# ST_LINK_V2-1.net
KiCad netlist of a schematic drawn in Altium Designer
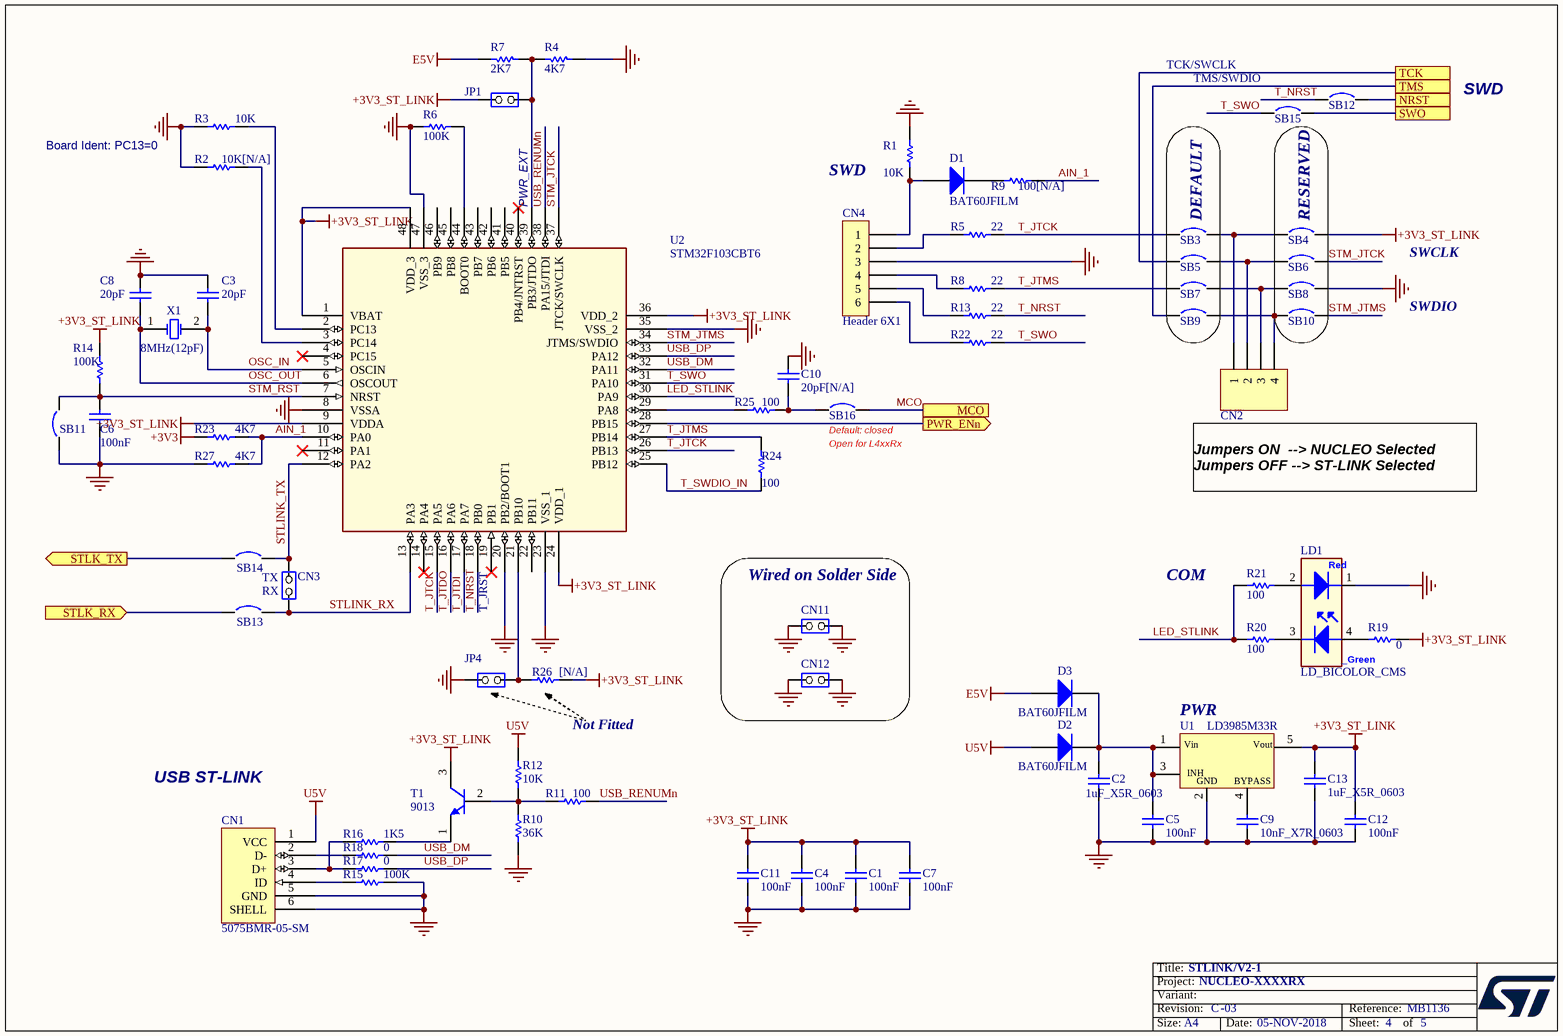
[diagram p0: ST_LINK_V2-1.SCHDOC]

(export (version "E")
  (design (tool "Eeschema 10.0.6"))
  (components
    (comp (ref "C1")
      (value "100nF")
      (footprint "0603C")
      (description "Capacitor 0402 / 0603 / 0805")
      (libsource (lib "MCD_TOOLS") (part "Capacitor_ST"))
    )
    (comp (ref "C2")
      (value "1uF_X5R_0603")
      (footprint "0603C")
      (description "0603  X5R 1µF")
      (fields (field (name "TOLERANCE") "10%"))
      (libsource (lib "MB963_1") (part "CAP SMD 0603  X5R 1µF 25V 10%"))
    )
    (comp (ref "C3")
      (value "20pF")
      (footprint "0603C")
      (description "Capacitor 0402 / 0603 / 0805")
      (libsource (lib "MCD_TOOLS") (part "Capacitor_ST"))
    )
    (comp (ref "C4")
      (value "100nF")
      (footprint "0603C")
      (description "Capacitor 0402 / 0603 / 0805")
      (libsource (lib "MCD_TOOLS") (part "Capacitor_ST"))
    )
    (comp (ref "C5")
      (value "100nF")
      (footprint "0603C")
      (description "Capacitor 0402 / 0603 / 0805")
      (libsource (lib "MCD_TOOLS") (part "Capacitor_ST"))
    )
    (comp (ref "C6")
      (value "100nF")
      (footprint "0603C")
      (description "Capacitor 0402 / 0603 / 0805")
      (libsource (lib "MCD_TOOLS") (part "Capacitor_ST"))
    )
    (comp (ref "C7")
      (value "100nF")
      (footprint "0603C")
      (description "Capacitor 0402 / 0603 / 0805")
      (libsource (lib "MCD_TOOLS") (part "Capacitor_ST"))
    )
    (comp (ref "C8")
      (value "20pF")
      (footprint "0603C")
      (description "Capacitor 0402 / 0603 / 0805")
      (libsource (lib "MCD_TOOLS") (part "Capacitor_ST"))
    )
    (comp (ref "C9")
      (value "10nF_X7R_0603")
      (footprint "0603C")
      (description "0603  X7R 10NF")
      (fields (field (name "TOLERANCE") "10%"))
      (libsource (lib "MB963_1") (part "CAP SMD 0603  X7R 10000PF 50V 10%"))
    )
    (comp (ref "C10")
      (value "20pF[N/A]")
      (footprint "0603C")
      (description "Capacitor 0402 / 0603 / 0805")
      (libsource (lib "MCD_TOOLS") (part "Capacitor_ST"))
    )
    (comp (ref "C11")
      (value "100nF")
      (footprint "0603C")
      (description "Capacitor 0402 / 0603 / 0805")
      (libsource (lib "MCD_TOOLS") (part "Capacitor_ST"))
    )
    (comp (ref "C12")
      (value "100nF")
      (footprint "0603C")
      (description "Capacitor 0402 / 0603 / 0805")
      (libsource (lib "MCD_TOOLS") (part "Capacitor_ST"))
    )
    (comp (ref "C13")
      (value "1uF_X5R_0603")
      (footprint "0603C")
      (description "0603  X5R 1µF")
      (fields (field (name "TOLERANCE") "10%"))
      (libsource (lib "MB963_1") (part "CAP SMD 0603  X5R 1µF 25V 10%"))
    )
    (comp (ref "CN1")
      (value "5075BMR-05-SM")
      (footprint "USB-MINI-B-SMD")
      (description "USB-MINI-typeB connector")
      (libsource (lib "MCD_TOOLS") (part "USB-MINI-typeB connector"))
    )
    (comp (ref "CN2")
      (value "Header 4")
      (footprint "1*4")
      (description "Header, 4-Pin, Single row")
      (fields (field (name "PUBLISHER") "Altium Limited"))
      (libsource (lib "Nucleo_64") (part "Header 4"))
    )
    (comp (ref "CN3") (value "~") (footprint "SIP2/2.54") (libsource (lib "MCD_TOOLS") (part "JP2")))
    (comp (ref "CN4")
      (value "Header 6X1")
      (footprint "1*6P")
      (description "Header, 6-Pin, Single row")
      (fields (field (name "PUBLISHER") "Altium Limited"))
      (libsource (lib "Nucleo_64") (part "Header 6X1"))
    )
    (comp (ref "CN11") (value "~") (footprint "SIP2/2.54") (libsource (lib "*") (part "JP2")))
    (comp (ref "CN12") (value "~") (footprint "SIP2/2.54") (libsource (lib "*") (part "JP2")))
    (comp (ref "D1")
      (value "BAT60JFILM")
      (footprint "SOD323/A")
      (libsource (lib "MCD_TOOLS") (part "BAT60JFILM"))
    )
    (comp (ref "D2")
      (value "BAT60JFILM")
      (footprint "SOD323/A")
      (libsource (lib "MCD_TOOLS") (part "BAT60JFILM"))
    )
    (comp (ref "D3")
      (value "BAT60JFILM")
      (footprint "SOD323/A")
      (libsource (lib "MCD_TOOLS") (part "BAT60JFILM"))
    )
    (comp (ref "JP1") (value "~") (footprint "SIP2/2.54") (libsource (lib "*") (part "JP2")))
    (comp (ref "JP4") (value "~") (footprint "SIP2/2.54") (libsource (lib "*") (part "JP2")))
    (comp (ref "LD1")
      (value "LD_BICOLOR_CMS")
      (footprint "HSMF-A201")
      (description "Bicolor Led")
      (libsource (lib "MB1136") (part "LD_BICOLOR_CMS"))
    )
    (comp (ref "R1")
      (value "10K")
      (footprint "0603R")
      (description "Resistor 0402 / 0603 / 0805")
      (libsource (lib "Miscellaneous Devices") (part "Res1"))
    )
    (comp (ref "R2")
      (value "10K[N/A]")
      (footprint "0603R")
      (description "Resistor 0402 / 0603 / 0805")
      (libsource (lib "Miscellaneous Devices") (part "Res1"))
    )
    (comp (ref "R3")
      (value "10K")
      (footprint "0603R")
      (description "Resistor 0402 / 0603 / 0805")
      (libsource (lib "Miscellaneous Devices") (part "Res1"))
    )
    (comp (ref "R4")
      (value "4K7")
      (footprint "0603R")
      (description "Resistor")
      (fields (field (name "PUBLISHER") "Altium Limited"))
      (libsource (lib "") (part "Res1_2"))
    )
    (comp (ref "R5")
      (value "22")
      (footprint "0603R")
      (description "Resistor 0402 / 0603 / 0805")
      (libsource (lib "Miscellaneous Devices") (part "Res1"))
    )
    (comp (ref "R6")
      (value "100K")
      (footprint "0603R")
      (description "Resistor 0402 / 0603 / 0805")
      (libsource (lib "Miscellaneous Devices") (part "Res1"))
    )
    (comp (ref "R7")
      (value "2K7")
      (footprint "0603R")
      (description "Resistor")
      (fields (field (name "PUBLISHER") "Altium Limited"))
      (libsource (lib "") (part "Res1_2"))
    )
    (comp (ref "R8")
      (value "22")
      (footprint "0603R")
      (description "Resistor 0402 / 0603 / 0805")
      (libsource (lib "Miscellaneous Devices") (part "Res1"))
    )
    (comp (ref "R9")
      (value "100[N/A]")
      (footprint "0603R")
      (description "Resistor 0402 / 0603 / 0805")
      (libsource (lib "Miscellaneous Devices") (part "Res1"))
    )
    (comp (ref "R10")
      (value "36K")
      (footprint "0603R")
      (description "Resistor")
      (fields (field (name "PUBLISHER") "Altium Limited"))
      (libsource (lib "") (part "Res1_1"))
    )
    (comp (ref "R11")
      (value "100")
      (footprint "0603R")
      (description "Resistor 0402 / 0603 / 0805")
      (libsource (lib "Miscellaneous Devices") (part "Res1"))
    )
    (comp (ref "R12")
      (value "10K")
      (footprint "0603R")
      (description "Resistor")
      (fields (field (name "PUBLISHER") "Altium Limited"))
      (libsource (lib "") (part "Res1_1"))
    )
    (comp (ref "R13")
      (value "22")
      (footprint "0603R")
      (description "Resistor 0402 / 0603 / 0805")
      (libsource (lib "Miscellaneous Devices") (part "Res1"))
    )
    (comp (ref "R14")
      (value "100K")
      (footprint "0603R")
      (description "Resistor 0402 / 0603 / 0805")
      (libsource (lib "Miscellaneous Devices") (part "Res1"))
    )
    (comp (ref "R15")
      (value "100K")
      (footprint "0603R")
      (description "Resistor 0402 / 0603 / 0805")
      (libsource (lib "Miscellaneous Devices") (part "Res1"))
    )
    (comp (ref "R16")
      (value "1K5")
      (footprint "0603R")
      (description "Resistor 0402 / 0603 / 0805")
      (libsource (lib "Miscellaneous Devices") (part "Res1"))
    )
    (comp (ref "R17")
      (value "0")
      (footprint "0603R")
      (description "Resistor 0402 / 0603 / 0805")
      (libsource (lib "Miscellaneous Devices") (part "Res1"))
    )
    (comp (ref "R18")
      (value "0")
      (footprint "0603R")
      (description "Resistor 0402 / 0603 / 0805")
      (libsource (lib "Miscellaneous Devices") (part "Res1"))
    )
    (comp (ref "R19")
      (value "0")
      (footprint "0603R")
      (description "Resistor 0402 / 0603 / 0805")
      (libsource (lib "Miscellaneous Devices") (part "Res1"))
    )
    (comp (ref "R20")
      (value "100")
      (footprint "0603R")
      (description "Resistor 0402 / 0603 / 0805")
      (libsource (lib "Miscellaneous Devices") (part "Res1"))
    )
    (comp (ref "R21")
      (value "100")
      (footprint "0603R")
      (description "Resistor 0402 / 0603 / 0805")
      (libsource (lib "Miscellaneous Devices") (part "Res1"))
    )
    (comp (ref "R22")
      (value "22")
      (footprint "0603R")
      (description "Resistor 0402 / 0603 / 0805")
      (libsource (lib "Miscellaneous Devices") (part "Res1"))
    )
    (comp (ref "R23")
      (value "4K7")
      (footprint "0603R")
      (description "Resistor 0402 / 0603 / 0805")
      (libsource (lib "Miscellaneous Devices") (part "Res1"))
    )
    (comp (ref "R24")
      (value "100")
      (footprint "0603R")
      (description "Resistor 0402 / 0603 / 0805")
      (libsource (lib "Miscellaneous Devices") (part "Res1"))
    )
    (comp (ref "R25")
      (value "100")
      (footprint "0603R")
      (description "Resistor 0402 / 0603 / 0805")
      (libsource (lib "Miscellaneous Devices") (part "Res1"))
    )
    (comp (ref "R26")
      (value "[N/A]")
      (footprint "0603R")
      (description "Resistor")
      (fields (field (name "PUBLISHER") "Altium Limited"))
      (libsource (lib "") (part "Res1_1"))
    )
    (comp (ref "R27")
      (value "4K7")
      (footprint "0603R")
      (description "Resistor 0402 / 0603 / 0805")
      (libsource (lib "Miscellaneous Devices") (part "Res1"))
    )
    (comp (ref "SB3")
      (value "Circuit Breaker")
      (footprint "JP2_SMD")
      (fields (field (name "PUBLISHER") "Altium Limited"))
      (libsource (lib "MB915") (part "Circuit Breaker"))
    )
    (comp (ref "SB4")
      (value "Circuit Breaker")
      (footprint "JP2_SMD")
      (fields (field (name "PUBLISHER") "Altium Limited"))
      (libsource (lib "MB915") (part "Circuit Breaker"))
    )
    (comp (ref "SB5")
      (value "Circuit Breaker")
      (footprint "JP2_SMD")
      (fields (field (name "PUBLISHER") "Altium Limited"))
      (libsource (lib "MB915") (part "Circuit Breaker"))
    )
    (comp (ref "SB6")
      (value "Circuit Breaker")
      (footprint "JP2_SMD")
      (fields (field (name "PUBLISHER") "Altium Limited"))
      (libsource (lib "MB915") (part "Circuit Breaker"))
    )
    (comp (ref "SB7")
      (value "Circuit Breaker")
      (footprint "JP2_SMD")
      (fields (field (name "PUBLISHER") "Altium Limited"))
      (libsource (lib "MB915") (part "Circuit Breaker"))
    )
    (comp (ref "SB8")
      (value "Circuit Breaker")
      (footprint "JP2_SMD")
      (fields (field (name "PUBLISHER") "Altium Limited"))
      (libsource (lib "MB915") (part "Circuit Breaker"))
    )
    (comp (ref "SB9")
      (value "Circuit Breaker")
      (footprint "JP2_SMD")
      (fields (field (name "PUBLISHER") "Altium Limited"))
      (libsource (lib "MB915") (part "Circuit Breaker"))
    )
    (comp (ref "SB10")
      (value "Circuit Breaker")
      (footprint "JP2_SMD")
      (fields (field (name "PUBLISHER") "Altium Limited"))
      (libsource (lib "MB915") (part "Circuit Breaker"))
    )
    (comp (ref "SB11")
      (value "Circuit Breaker")
      (footprint "JP2_SMD")
      (fields (field (name "PUBLISHER") "Altium Limited"))
      (libsource (lib "MB915") (part "Circuit Breaker"))
    )
    (comp (ref "SB12")
      (value "Circuit Breaker")
      (footprint "JP2_SMD")
      (fields (field (name "PUBLISHER") "Altium Limited"))
      (libsource (lib "MB915") (part "Circuit Breaker"))
    )
    (comp (ref "SB13")
      (value "Circuit Breaker")
      (footprint "JP2_SMD")
      (fields (field (name "PUBLISHER") "Altium Limited"))
      (libsource (lib "MCD_TOOLS") (part "Circuit Breaker"))
    )
    (comp (ref "SB14")
      (value "Circuit Breaker")
      (footprint "JP2_SMD")
      (fields (field (name "PUBLISHER") "Altium Limited"))
      (libsource (lib "MCD_TOOLS") (part "Circuit Breaker"))
    )
    (comp (ref "SB15")
      (value "Circuit Breaker")
      (footprint "JP2_SMD")
      (fields (field (name "PUBLISHER") "Altium Limited"))
      (libsource (lib "MCD_TOOLS") (part "Circuit Breaker"))
    )
    (comp (ref "SB16")
      (value "Circuit Breaker")
      (footprint "JP2_SMD")
      (fields (field (name "PUBLISHER") "Altium Limited"))
      (libsource (lib "MCD_TOOLS") (part "Circuit Breaker"))
    )
    (comp (ref "T1")
      (value "9013")
      (footprint "SOT-23")
      (description "NPN Bipolar Transistor")
      (fields (field (name "PUBLISHER") "Altium Limited"))
      (libsource (lib "Miscellaneous Devices") (part "NPN"))
    )
    (comp (ref "U1")
      (value "LD3985M33R")
      (footprint "SOT-23-5L")
      (description "Ultra low drop-low noise BiCMOS voltage, regulators low ESR capacitors compatible")
      (libsource (lib "MCD_TOOLS") (part "LD3985M33R"))
    )
    (comp (ref "U2")
      (value "STM32F103CBT6")
      (footprint "QFP48 7X7")
      (description "Medium-density performance line ARM-based 32-bit MCU with 64KB Flash")
      (libsource (lib "Nucleo_64") (part "STM32F103CBT6"))
    )
    (comp (ref "X1")
      (value "8MHz(12pF)")
      (footprint "XTAL1")
      (description "Crystal Oscillator")
      (fields (field (name "PUBLISHER") "Altium Limited"))
      (libsource (lib "MB963_1") (part "XTAL"))
    )
  )
  (nets
    (net (code "1") (name "+3V3") (class "Default")
      (node (ref "R23") (pin "1") (pinfunction "1_1") (pintype "passive"))
    )
    (net (code "2") (name "+3V3_ST_LINK") (class "Default")
      (node (ref "C1") (pin "2") (pinfunction "2_2") (pintype "passive"))
      (node (ref "C11") (pin "2") (pinfunction "2_2") (pintype "passive"))
      (node (ref "C12") (pin "2") (pinfunction "2_2") (pintype "passive"))
      (node (ref "C13") (pin "1") (pinfunction "1_1") (pintype "passive"))
      (node (ref "C4") (pin "2") (pinfunction "2_2") (pintype "passive"))
      (node (ref "C7") (pin "2") (pinfunction "2_2") (pintype "passive"))
      (node (ref "JP1") (pin "1") (pinfunction "COMMON_1") (pintype "passive"))
      (node (ref "R14") (pin "2") (pinfunction "2_2") (pintype "passive"))
      (node (ref "R19") (pin "2") (pinfunction "2_2") (pintype "passive"))
      (node (ref "R26") (pin "1") (pinfunction "1_1") (pintype "passive"))
      (node (ref "SB4") (pin "2") (pinfunction "2_2") (pintype "passive"))
      (node (ref "T1") (pin "3") (pinfunction "C_3") (pintype "passive"))
      (node (ref "U1") (pin "5") (pinfunction "Vout_5") (pintype "passive"))
      (node (ref "U2") (pin "1") (pinfunction "VBAT_1") (pintype "power_in"))
      (node (ref "U2") (pin "24") (pinfunction "VDD_1_24") (pintype "power_in"))
      (node (ref "U2") (pin "36") (pinfunction "VDD_2_36") (pintype "power_in"))
      (node (ref "U2") (pin "48") (pinfunction "VDD_3_48") (pintype "power_in"))
      (node (ref "U2") (pin "9") (pinfunction "VDDA_9") (pintype "power_in"))
    )
    (net (code "3") (name "/AIN_1") (class "Default")
      (node (ref "R23") (pin "2") (pinfunction "2_2") (pintype "passive"))
      (node (ref "R27") (pin "2") (pinfunction "2_2") (pintype "passive"))
      (node (ref "R9") (pin "2") (pinfunction "2_2") (pintype "passive"))
      (node (ref "U2") (pin "10") (pinfunction "PA0_10") (pintype "bidirectional"))
    )
    (net (code "4") (name "/LED_STLINK") (class "Default")
      (node (ref "R20") (pin "1") (pinfunction "1_1") (pintype "passive"))
      (node (ref "R21") (pin "1") (pinfunction "1_1") (pintype "passive"))
      (node (ref "U2") (pin "30") (pinfunction "PA9_30") (pintype "bidirectional"))
    )
    (net (code "5") (name "/MCO") (class "Default")
      (node (ref "SB16") (pin "2") (pinfunction "2_2") (pintype "passive"))
    )
    (net (code "6") (name "/NRST") (class "Default")
      (node (ref "SB12") (pin "2") (pinfunction "2_2") (pintype "passive"))
    )
    (net (code "7") (name "/OSC_IN") (class "Default")
      (node (ref "C3") (pin "1") (pinfunction "1_1") (pintype "passive"))
      (node (ref "U2") (pin "5") (pinfunction "OSCIN_5") (pintype "input"))
      (node (ref "X1") (pin "2") (pinfunction "OSC2_2") (pintype "passive"))
    )
    (net (code "8") (name "/OSC_OUT") (class "Default")
      (node (ref "C8") (pin "1") (pinfunction "1_1") (pintype "passive"))
      (node (ref "U2") (pin "6") (pinfunction "OSCOUT_6") (pintype "output"))
      (node (ref "X1") (pin "1") (pinfunction "OSC1_1") (pintype "passive"))
    )
    (net (code "9") (name "/PWR_ENn") (class "Default")
      (node (ref "U2") (pin "28") (pinfunction "PB15_28") (pintype "bidirectional"))
    )
    (net (code "10") (name "/STLINK_RX") (class "Default")
      (node (ref "CN3") (pin "1") (pinfunction "COMMON_1") (pintype "passive"))
      (node (ref "SB13") (pin "2") (pinfunction "2_2") (pintype "passive"))
      (node (ref "U2") (pin "13") (pinfunction "PA3_13") (pintype "bidirectional"))
    )
    (net (code "11") (name "/STLINK_TX") (class "Default")
      (node (ref "CN3") (pin "2") (pinfunction "NO_2") (pintype "passive"))
      (node (ref "SB14") (pin "2") (pinfunction "2_2") (pintype "passive"))
      (node (ref "U2") (pin "12") (pinfunction "PA2_12") (pintype "bidirectional"))
    )
    (net (code "12") (name "/STLK_RX") (class "Default")
      (node (ref "SB13") (pin "1") (pinfunction "1_1") (pintype "passive"))
    )
    (net (code "13") (name "/STLK_TX") (class "Default")
      (node (ref "SB14") (pin "1") (pinfunction "1_1") (pintype "passive"))
    )
    (net (code "14") (name "/STM_JTCK") (class "Default")
      (node (ref "SB6") (pin "2") (pinfunction "2_2") (pintype "passive"))
      (node (ref "U2") (pin "37") (pinfunction "JTCK/SWCLK_37") (pintype "bidirectional"))
    )
    (net (code "15") (name "/STM_JTMS") (class "Default")
      (node (ref "SB10") (pin "2") (pinfunction "2_2") (pintype "passive"))
      (node (ref "U2") (pin "34") (pinfunction "JTMS/SWDIO_34") (pintype "bidirectional"))
    )
    (net (code "16") (name "/STM_RST") (class "Default")
      (node (ref "C6") (pin "2") (pinfunction "2_2") (pintype "passive"))
      (node (ref "R14") (pin "1") (pinfunction "1_1") (pintype "passive"))
      (node (ref "SB11") (pin "2") (pinfunction "2_2") (pintype "passive"))
      (node (ref "U2") (pin "7") (pinfunction "NRST_7") (pintype "input"))
    )
    (net (code "17") (name "/SWO") (class "Default")
      (node (ref "SB15") (pin "2") (pinfunction "2_2") (pintype "passive"))
    )
    (net (code "18") (name "/TCK") (class "Default")
      (node (ref "SB5") (pin "1") (pinfunction "1_1") (pintype "passive"))
    )
    (net (code "19") (name "/TMS") (class "Default")
      (node (ref "SB9") (pin "1") (pinfunction "1_1") (pintype "passive"))
    )
    (net (code "20") (name "/T_JTCK") (class "Default")
      (node (ref "R5") (pin "2") (pinfunction "2_2") (pintype "passive"))
      (node (ref "SB3") (pin "1") (pinfunction "1_1") (pintype "passive"))
      (node (ref "U2") (pin "15") (pinfunction "PA5_15") (pintype "bidirectional"))
      (node (ref "U2") (pin "26") (pinfunction "PB13_26") (pintype "bidirectional"))
    )
    (net (code "21") (name "/T_JTDI") (class "Default")
      (node (ref "U2") (pin "17") (pinfunction "PA7_17") (pintype "bidirectional"))
    )
    (net (code "22") (name "/T_JTDO") (class "Default")
      (node (ref "U2") (pin "16") (pinfunction "PA6_16") (pintype "bidirectional"))
    )
    (net (code "23") (name "/T_JTMS") (class "Default")
      (node (ref "R24") (pin "2") (pinfunction "2_2") (pintype "passive"))
      (node (ref "R8") (pin "2") (pinfunction "2_2") (pintype "passive"))
      (node (ref "SB7") (pin "1") (pinfunction "1_1") (pintype "passive"))
      (node (ref "U2") (pin "27") (pinfunction "PB14_27") (pintype "bidirectional"))
    )
    (net (code "24") (name "/T_NRST") (class "Default")
      (node (ref "R13") (pin "2") (pinfunction "2_2") (pintype "passive"))
      (node (ref "SB12") (pin "1") (pinfunction "1_1") (pintype "passive"))
      (node (ref "U2") (pin "18") (pinfunction "PB0_18") (pintype "bidirectional"))
    )
    (net (code "25") (name "/T_SWDIO_IN") (class "Default")
      (node (ref "R24") (pin "1") (pinfunction "1_1") (pintype "passive"))
      (node (ref "U2") (pin "25") (pinfunction "PB12_25") (pintype "bidirectional"))
    )
    (net (code "26") (name "/T_SWO") (class "Default")
      (node (ref "R22") (pin "2") (pinfunction "2_2") (pintype "passive"))
      (node (ref "SB15") (pin "1") (pinfunction "1_1") (pintype "passive"))
      (node (ref "U2") (pin "31") (pinfunction "PA10_31") (pintype "bidirectional"))
    )
    (net (code "27") (name "/USB_DM") (class "Default")
      (node (ref "R18") (pin "2") (pinfunction "2_2") (pintype "passive"))
      (node (ref "U2") (pin "32") (pinfunction "PA11_32") (pintype "bidirectional"))
    )
    (net (code "28") (name "/USB_DP") (class "Default")
      (node (ref "R17") (pin "2") (pinfunction "2_2") (pintype "passive"))
      (node (ref "U2") (pin "33") (pinfunction "PA12_33") (pintype "bidirectional"))
    )
    (net (code "29") (name "/USB_RENUMn") (class "Default")
      (node (ref "R11") (pin "2") (pinfunction "2_2") (pintype "passive"))
      (node (ref "U2") (pin "38") (pinfunction "PA15/JTDI_38") (pintype "bidirectional"))
    )
    (net (code "30") (name "E5V") (class "Default")
      (node (ref "D3") (pin "1") (pinfunction "A_1") (pintype "passive"))
      (node (ref "R7") (pin "1") (pinfunction "1_1") (pintype "passive"))
    )
    (net (code "31") (name "GND") (class "Default")
      (node (ref "C1") (pin "1") (pinfunction "1_1") (pintype "passive"))
      (node (ref "C10") (pin "2") (pinfunction "2_2") (pintype "passive"))
      (node (ref "C11") (pin "1") (pinfunction "1_1") (pintype "passive"))
      (node (ref "C12") (pin "1") (pinfunction "1_1") (pintype "passive"))
      (node (ref "C13") (pin "2") (pinfunction "2_2") (pintype "passive"))
      (node (ref "C2") (pin "1") (pinfunction "1_1") (pintype "passive"))
      (node (ref "C3") (pin "2") (pinfunction "2_2") (pintype "passive"))
      (node (ref "C4") (pin "1") (pinfunction "1_1") (pintype "passive"))
      (node (ref "C5") (pin "1") (pinfunction "1_1") (pintype "passive"))
      (node (ref "C6") (pin "1") (pinfunction "1_1") (pintype "passive"))
      (node (ref "C7") (pin "1") (pinfunction "1_1") (pintype "passive"))
      (node (ref "C8") (pin "2") (pinfunction "2_2") (pintype "passive"))
      (node (ref "C9") (pin "1") (pinfunction "1_1") (pintype "passive"))
      (node (ref "CN1") (pin "5") (pinfunction "GND_5") (pintype "power_in"))
      (node (ref "CN1") (pin "6") (pinfunction "SHELL_6") (pintype "power_in"))
      (node (ref "CN11") (pin "1") (pinfunction "COMMON_1") (pintype "passive"))
      (node (ref "CN11") (pin "2") (pinfunction "NO_2") (pintype "passive"))
      (node (ref "CN12") (pin "1") (pinfunction "COMMON_1") (pintype "passive"))
      (node (ref "CN12") (pin "2") (pinfunction "NO_2") (pintype "passive"))
      (node (ref "CN4") (pin "3") (pinfunction "3_3") (pintype "passive"))
      (node (ref "JP4") (pin "1") (pinfunction "COMMON_1") (pintype "passive"))
      (node (ref "LD1") (pin "1") (pinfunction "1_1") (pintype "passive"))
      (node (ref "R1") (pin "2") (pinfunction "2_2") (pintype "passive"))
      (node (ref "R10") (pin "1") (pinfunction "1_1") (pintype "passive"))
      (node (ref "R15") (pin "2") (pinfunction "2_2") (pintype "passive"))
      (node (ref "R2") (pin "1") (pinfunction "1_1") (pintype "passive"))
      (node (ref "R27") (pin "1") (pinfunction "1_1") (pintype "passive"))
      (node (ref "R3") (pin "1") (pinfunction "1_1") (pintype "passive"))
      (node (ref "R4") (pin "2") (pinfunction "2_2") (pintype "passive"))
      (node (ref "R6") (pin "1") (pinfunction "1_1") (pintype "passive"))
      (node (ref "SB11") (pin "1") (pinfunction "1_1") (pintype "passive"))
      (node (ref "SB8") (pin "2") (pinfunction "2_2") (pintype "passive"))
      (node (ref "U1") (pin "2") (pinfunction "GND_2") (pintype "passive"))
      (node (ref "U2") (pin "20") (pinfunction "PB2/BOOT1_20") (pintype "bidirectional"))
      (node (ref "U2") (pin "23") (pinfunction "VSS_1_23") (pintype "power_in"))
      (node (ref "U2") (pin "35") (pinfunction "VSS_2_35") (pintype "power_in"))
      (node (ref "U2") (pin "47") (pinfunction "VSS_3_47") (pintype "power_in"))
      (node (ref "U2") (pin "8") (pinfunction "VSSA_8") (pintype "power_in"))
    )
    (net (code "32") (name "Net-(C10-Pad1)") (class "Default")
      (node (ref "C10") (pin "1") (pinfunction "1_1") (pintype "passive"))
      (node (ref "R25") (pin "2") (pinfunction "2_2") (pintype "passive"))
      (node (ref "SB16") (pin "1") (pinfunction "1_1") (pintype "passive"))
    )
    (net (code "33") (name "Net-(CN1-D+)") (class "Default")
      (node (ref "CN1") (pin "3") (pinfunction "D+_3") (pintype "bidirectional"))
      (node (ref "R16") (pin "1") (pinfunction "1_1") (pintype "passive"))
      (node (ref "R17") (pin "1") (pinfunction "1_1") (pintype "passive"))
    )
    (net (code "34") (name "Net-(CN1-D-)") (class "Default")
      (node (ref "CN1") (pin "2") (pinfunction "D-_2") (pintype "bidirectional"))
      (node (ref "R18") (pin "1") (pinfunction "1_1") (pintype "passive"))
    )
    (net (code "35") (name "Net-(CN1-ID)") (class "Default")
      (node (ref "CN1") (pin "4") (pinfunction "ID_4") (pintype "input"))
      (node (ref "R15") (pin "1") (pinfunction "1_1") (pintype "passive"))
    )
    (net (code "36") (name "Net-(CN2-Pad1)") (class "Default")
      (node (ref "CN2") (pin "1") (pinfunction "1_1") (pintype "passive"))
      (node (ref "SB3") (pin "2") (pinfunction "2_2") (pintype "passive"))
      (node (ref "SB4") (pin "1") (pinfunction "1_1") (pintype "passive"))
    )
    (net (code "37") (name "Net-(CN2-Pad2)") (class "Default")
      (node (ref "CN2") (pin "2") (pinfunction "2_2") (pintype "passive"))
      (node (ref "SB5") (pin "2") (pinfunction "2_2") (pintype "passive"))
      (node (ref "SB6") (pin "1") (pinfunction "1_1") (pintype "passive"))
    )
    (net (code "38") (name "Net-(CN2-Pad3)") (class "Default")
      (node (ref "CN2") (pin "3") (pinfunction "3_3") (pintype "passive"))
      (node (ref "SB7") (pin "2") (pinfunction "2_2") (pintype "passive"))
      (node (ref "SB8") (pin "1") (pinfunction "1_1") (pintype "passive"))
    )
    (net (code "39") (name "Net-(CN2-Pad4)") (class "Default")
      (node (ref "CN2") (pin "4") (pinfunction "4_4") (pintype "passive"))
      (node (ref "SB10") (pin "1") (pinfunction "1_1") (pintype "passive"))
      (node (ref "SB9") (pin "2") (pinfunction "2_2") (pintype "passive"))
    )
    (net (code "40") (name "Net-(CN4-Pad2)") (class "Default")
      (node (ref "CN4") (pin "2") (pinfunction "2_2") (pintype "passive"))
      (node (ref "R5") (pin "1") (pinfunction "1_1") (pintype "passive"))
    )
    (net (code "41") (name "Net-(CN4-Pad4)") (class "Default")
      (node (ref "CN4") (pin "4") (pinfunction "4_4") (pintype "passive"))
      (node (ref "R8") (pin "1") (pinfunction "1_1") (pintype "passive"))
    )
    (net (code "42") (name "Net-(CN4-Pad5)") (class "Default")
      (node (ref "CN4") (pin "5") (pinfunction "5_5") (pintype "passive"))
      (node (ref "R13") (pin "1") (pinfunction "1_1") (pintype "passive"))
    )
    (net (code "43") (name "Net-(CN4-Pad6)") (class "Default")
      (node (ref "CN4") (pin "6") (pinfunction "6_6") (pintype "passive"))
      (node (ref "R22") (pin "1") (pinfunction "1_1") (pintype "passive"))
    )
    (net (code "44") (name "Net-(D1-A)") (class "Default")
      (node (ref "CN4") (pin "1") (pinfunction "1_1") (pintype "passive"))
      (node (ref "D1") (pin "1") (pinfunction "A_1") (pintype "passive"))
      (node (ref "R1") (pin "1") (pinfunction "1_1") (pintype "passive"))
    )
    (net (code "45") (name "Net-(D1-K)") (class "Default")
      (node (ref "D1") (pin "2") (pinfunction "K_2") (pintype "passive"))
      (node (ref "R9") (pin "1") (pinfunction "1_1") (pintype "passive"))
    )
    (net (code "46") (name "Net-(D2-K)") (class "Default")
      (node (ref "C2") (pin "2") (pinfunction "2_2") (pintype "passive"))
      (node (ref "C5") (pin "2") (pinfunction "2_2") (pintype "passive"))
      (node (ref "D2") (pin "2") (pinfunction "K_2") (pintype "passive"))
      (node (ref "D3") (pin "2") (pinfunction "K_2") (pintype "passive"))
      (node (ref "U1") (pin "1") (pinfunction "Vin_1") (pintype "passive"))
      (node (ref "U1") (pin "3") (pinfunction "CE_3") (pintype "passive"))
    )
    (net (code "47") (name "Net-(JP1-NO)") (class "Default")
      (node (ref "JP1") (pin "2") (pinfunction "NO_2") (pintype "passive"))
      (node (ref "R4") (pin "1") (pinfunction "1_1") (pintype "passive"))
      (node (ref "R7") (pin "2") (pinfunction "2_2") (pintype "passive"))
      (node (ref "U2") (pin "39") (pinfunction "PB3/JTDO_39") (pintype "bidirectional"))
    )
    (net (code "48") (name "Net-(JP4-NO)") (class "Default")
      (node (ref "JP4") (pin "2") (pinfunction "NO_2") (pintype "passive"))
      (node (ref "R26") (pin "2") (pinfunction "2_2") (pintype "passive"))
      (node (ref "U2") (pin "21") (pinfunction "PB10_21") (pintype "bidirectional"))
    )
    (net (code "49") (name "Net-(LD1-Pad2)") (class "Default")
      (node (ref "LD1") (pin "2") (pinfunction "2_2") (pintype "passive"))
      (node (ref "R21") (pin "2") (pinfunction "2_2") (pintype "passive"))
    )
    (net (code "50") (name "Net-(LD1-Pad3)") (class "Default")
      (node (ref "LD1") (pin "3") (pinfunction "3_3") (pintype "passive"))
      (node (ref "R20") (pin "2") (pinfunction "2_2") (pintype "passive"))
    )
    (net (code "51") (name "Net-(LD1-Pad4)") (class "Default")
      (node (ref "LD1") (pin "4") (pinfunction "4_4") (pintype "passive"))
      (node (ref "R19") (pin "1") (pinfunction "1_1") (pintype "passive"))
    )
    (net (code "52") (name "Net-(T1-B)") (class "Default")
      (node (ref "R10") (pin "2") (pinfunction "2_2") (pintype "passive"))
      (node (ref "R11") (pin "1") (pinfunction "1_1") (pintype "passive"))
      (node (ref "R12") (pin "1") (pinfunction "1_1") (pintype "passive"))
      (node (ref "T1") (pin "2") (pinfunction "B_2") (pintype "passive"))
    )
    (net (code "53") (name "Net-(T1-E)") (class "Default")
      (node (ref "R16") (pin "2") (pinfunction "2_2") (pintype "passive"))
      (node (ref "T1") (pin "1") (pinfunction "E_1") (pintype "passive"))
    )
    (net (code "54") (name "Net-(U1-BYPASS)") (class "Default")
      (node (ref "C9") (pin "2") (pinfunction "2_2") (pintype "passive"))
      (node (ref "U1") (pin "4") (pinfunction "BYPASS_4") (pintype "passive"))
    )
    (net (code "55") (name "Net-(U2-BOOT0)") (class "Default")
      (node (ref "R6") (pin "2") (pinfunction "2_2") (pintype "passive"))
      (node (ref "U2") (pin "44") (pinfunction "BOOT0_44") (pintype "bidirectional"))
    )
    (net (code "56") (name "Net-(U2-PA8)") (class "Default")
      (node (ref "R25") (pin "1") (pinfunction "1_1") (pintype "passive"))
      (node (ref "U2") (pin "29") (pinfunction "PA8_29") (pintype "bidirectional"))
    )
    (net (code "57") (name "Net-(U2-PC13)") (class "Default")
      (node (ref "R3") (pin "2") (pinfunction "2_2") (pintype "passive"))
      (node (ref "U2") (pin "2") (pinfunction "PC13_2") (pintype "bidirectional"))
    )
    (net (code "58") (name "Net-(U2-PC14)") (class "Default")
      (node (ref "R2") (pin "2") (pinfunction "2_2") (pintype "passive"))
      (node (ref "U2") (pin "3") (pinfunction "PC14_3") (pintype "bidirectional"))
    )
    (net (code "59") (name "U5V") (class "Default")
      (node (ref "CN1") (pin "1") (pinfunction "VCC_1") (pintype "power_in"))
      (node (ref "D2") (pin "1") (pinfunction "A_1") (pintype "passive"))
      (node (ref "R12") (pin "2") (pinfunction "2_2") (pintype "passive"))
    )
    (net (code "60") (name "unconnected-(U2-PA1-Pad11)") (class "Default")
      (node (ref "U2") (pin "11") (pinfunction "PA1_11") (pintype "bidirectional+no_connect"))
    )
    (net (code "61") (name "unconnected-(U2-PA4-Pad14)") (class "Default")
      (node (ref "U2") (pin "14") (pinfunction "PA4_14") (pintype "bidirectional+no_connect"))
    )
    (net (code "62") (name "unconnected-(U2-PB1-Pad19)") (class "Default")
      (node (ref "U2") (pin "19") (pinfunction "PB1_19") (pintype "input+no_connect"))
    )
    (net (code "63") (name "unconnected-(U2-PB4{slash}JNTRST-Pad40)") (class "Default")
      (node (ref "U2") (pin "40") (pinfunction "PB4/JNTRST_40") (pintype "bidirectional+no_connect"))
    )
    (net (code "64") (name "unconnected-(U2-PB5-Pad41)") (class "Default")
      (node (ref "U2") (pin "41") (pinfunction "PB5_41") (pintype "bidirectional"))
    )
    (net (code "65") (name "unconnected-(U2-PB6-Pad42)") (class "Default")
      (node (ref "U2") (pin "42") (pinfunction "PB6_42") (pintype "bidirectional"))
    )
    (net (code "66") (name "unconnected-(U2-PB7-Pad43)") (class "Default")
      (node (ref "U2") (pin "43") (pinfunction "PB7_43") (pintype "bidirectional"))
    )
    (net (code "67") (name "unconnected-(U2-PB8-Pad45)") (class "Default")
      (node (ref "U2") (pin "45") (pinfunction "PB8_45") (pintype "bidirectional"))
    )
    (net (code "68") (name "unconnected-(U2-PB9-Pad46)") (class "Default")
      (node (ref "U2") (pin "46") (pinfunction "PB9_46") (pintype "bidirectional"))
    )
    (net (code "69") (name "unconnected-(U2-PB11-Pad22)") (class "Default")
      (node (ref "U2") (pin "22") (pinfunction "PB11_22") (pintype "bidirectional"))
    )
    (net (code "70") (name "unconnected-(U2-PC15-Pad4)") (class "Default")
      (node (ref "U2") (pin "4") (pinfunction "PC15_4") (pintype "bidirectional+no_connect"))
    )
  )
)
